# main.net
KiCad netlist of a schematic drawn in EAGLE
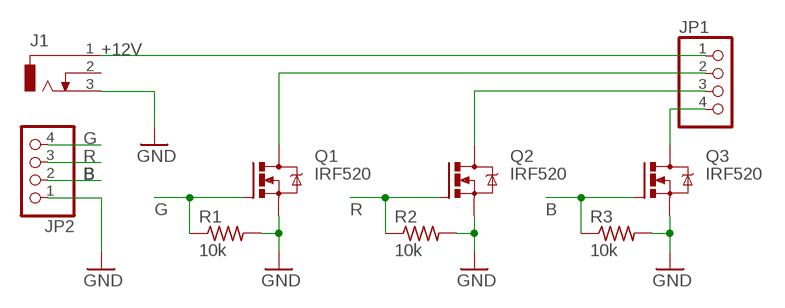
[diagram p0: schematic, sheet 1]

(export (version "E")
  (design (tool "Eeschema 10.0.6"))
  (components
    (comp (ref "J1")
      (value "DCJ0303")
      (footprint "eagle-import:DCJ0303")
      (libsource (lib "eagle-import") (part "DCJ0303"))
    )
    (comp (ref "JP1")
      (value "PINHD-1X4")
      (footprint "eagle-import:1X04")
      (libsource (lib "eagle-import") (part "PINHD-1X4"))
    )
    (comp (ref "JP2")
      (value "PINHD-1X4")
      (footprint "eagle-import:1X04")
      (libsource (lib "eagle-import") (part "PINHD-1X4"))
    )
    (comp (ref "Q1")
      (value "IRF520")
      (footprint "eagle-import:TO220BV")
      (libsource (lib "eagle-import") (part "IRF520"))
    )
    (comp (ref "Q2")
      (value "IRF520")
      (footprint "eagle-import:TO220BV")
      (libsource (lib "eagle-import") (part "IRF520"))
    )
    (comp (ref "Q3")
      (value "IRF520")
      (footprint "eagle-import:TO220BV")
      (libsource (lib "eagle-import") (part "IRF520"))
    )
    (comp (ref "R1")
      (value "10k")
      (footprint "eagle-import:0207_7")
      (libsource (lib "eagle-import") (part "R-US_0207/7"))
    )
    (comp (ref "R2")
      (value "10k")
      (footprint "eagle-import:0207_7")
      (libsource (lib "eagle-import") (part "R-US_0207/7"))
    )
    (comp (ref "R3")
      (value "10k")
      (footprint "eagle-import:0207_7")
      (libsource (lib "eagle-import") (part "R-US_0207/7"))
    )
  )
  (nets
    (net (code "1") (name "/+12V") (class "Default")
      (node (ref "J1") (pin "1") (pinfunction "1_1") (pintype "passive"))
      (node (ref "JP1") (pin "1") (pinfunction "1_1") (pintype "passive"))
    )
    (net (code "2") (name "/B") (class "Default")
      (node (ref "JP2") (pin "2") (pinfunction "2_2") (pintype "passive"))
      (node (ref "Q3") (pin "G") (pinfunction "G_G") (pintype "passive"))
      (node (ref "R3") (pin "1") (pinfunction "1_1") (pintype "passive"))
    )
    (net (code "3") (name "/G") (class "Default")
      (node (ref "JP2") (pin "4") (pinfunction "4_4") (pintype "passive"))
      (node (ref "Q1") (pin "G") (pinfunction "G_G") (pintype "passive"))
      (node (ref "R1") (pin "1") (pinfunction "1_1") (pintype "passive"))
    )
    (net (code "4") (name "/R") (class "Default")
      (node (ref "JP2") (pin "3") (pinfunction "3_3") (pintype "passive"))
      (node (ref "Q2") (pin "G") (pinfunction "G_G") (pintype "passive"))
      (node (ref "R2") (pin "1") (pinfunction "1_1") (pintype "passive"))
    )
    (net (code "5") (name "GND") (class "Default")
      (node (ref "J1") (pin "3") (pinfunction "3_3") (pintype "passive"))
      (node (ref "JP2") (pin "1") (pinfunction "1_1") (pintype "passive"))
      (node (ref "Q1") (pin "S") (pinfunction "S_S") (pintype "passive"))
      (node (ref "Q2") (pin "S") (pinfunction "S_S") (pintype "passive"))
      (node (ref "Q3") (pin "S") (pinfunction "S_S") (pintype "passive"))
      (node (ref "R1") (pin "2") (pinfunction "2_2") (pintype "passive"))
      (node (ref "R2") (pin "2") (pinfunction "2_2") (pintype "passive"))
      (node (ref "R3") (pin "2") (pinfunction "2_2") (pintype "passive"))
    )
    (net (code "6") (name "Net-(JP1-Pad2)") (class "Default")
      (node (ref "JP1") (pin "2") (pinfunction "2_2") (pintype "passive"))
      (node (ref "Q1") (pin "D") (pinfunction "D_D") (pintype "passive"))
    )
    (net (code "7") (name "Net-(JP1-Pad3)") (class "Default")
      (node (ref "JP1") (pin "3") (pinfunction "3_3") (pintype "passive"))
      (node (ref "Q2") (pin "D") (pinfunction "D_D") (pintype "passive"))
    )
    (net (code "8") (name "Net-(JP1-Pad4)") (class "Default")
      (node (ref "JP1") (pin "4") (pinfunction "4_4") (pintype "passive"))
      (node (ref "Q3") (pin "D") (pinfunction "D_D") (pintype "passive"))
    )
    (net (code "9") (name "unconnected-(J1-Pad2)") (class "Default")
      (node (ref "J1") (pin "2") (pinfunction "2_2") (pintype "passive"))
    )
  )
)
